# Sheet1.net
KiCad netlist of a schematic drawn in Altium Designer
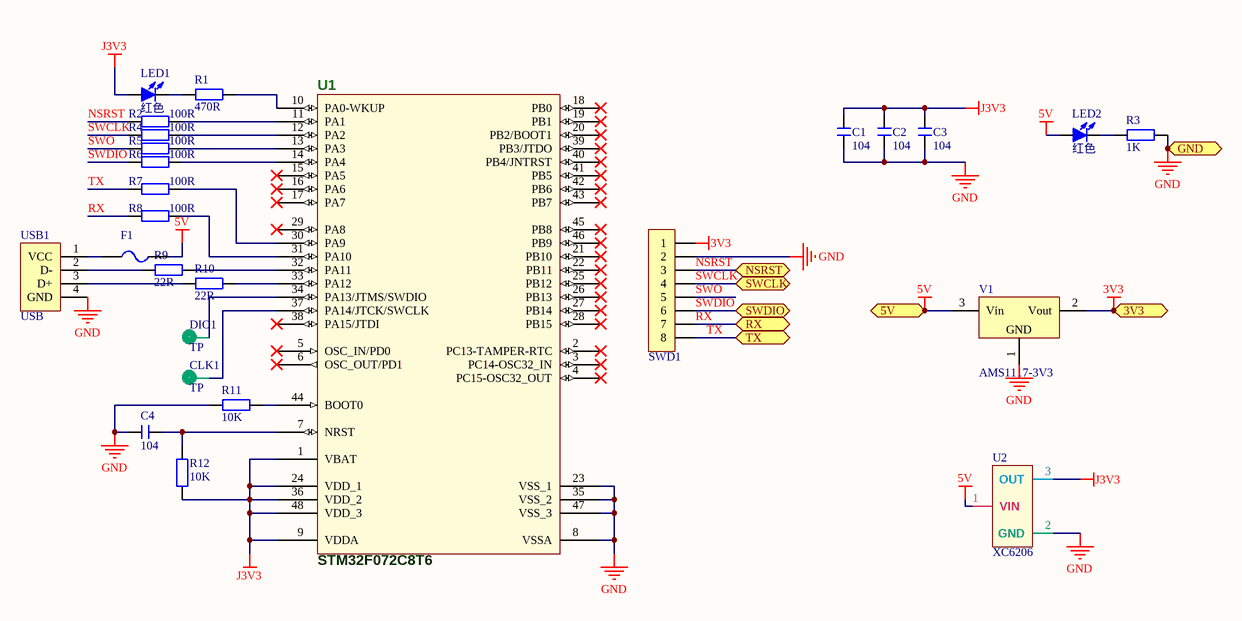
[diagram p0: Sheet1.SchDoc]

(export (version "E")
  (design (tool "Eeschema 10.0.6"))
  (components
    (comp (ref "C1")
      (value "104")
      (footprint "C 0805")
      (description "无极性贴片电容")
      (fields (field (name "版权归属") "黎明电子style"))
      (libsource (lib "电阻-电容-电感") (part "C"))
    )
    (comp (ref "C2")
      (value "104")
      (footprint "C 0805")
      (description "无极性贴片电容")
      (fields (field (name "版权归属") "黎明电子style"))
      (libsource (lib "电阻-电容-电感") (part "C"))
    )
    (comp (ref "C3")
      (value "104")
      (footprint "C 0805")
      (description "无极性贴片电容")
      (fields (field (name "版权归属") "黎明电子style"))
      (libsource (lib "电阻-电容-电感") (part "C"))
    )
    (comp (ref "C4")
      (value "104")
      (footprint "C 0805")
      (description "无极性贴片电容")
      (fields (field (name "版权归属") "黎明电子style"))
      (libsource (lib "电阻-电容-电感") (part "C"))
    )
    (comp (ref "CLK1") (value "TP") (footprint "TP") (libsource (lib "spotmini") (part "TP")))
    (comp (ref "DIO1") (value "TP") (footprint "TP") (libsource (lib "spotmini") (part "TP")))
    (comp (ref "F1")
      (value "~")
      (footprint "FU 0805")
      (description "贴片保险丝")
      (fields (field (name "版权归属") "黎明电子style"))
      (libsource (lib "保险丝-晶振") (part "FU"))
    )
    (comp (ref "LED1")
      (value "红色")
      (footprint "LED 0805G")
      (description "5mm草帽LED")
      (fields (field (name "版权归属") "黎明电子style"))
      (libsource (lib "LED") (part "LED-SH-5MM"))
    )
    (comp (ref "LED2")
      (value "红色")
      (footprint "LED 0805R")
      (description "5mm草帽LED")
      (fields (field (name "版权归属") "黎明电子style"))
      (libsource (lib "LED") (part "LED-SH-5MM"))
    )
    (comp (ref "R1")
      (value "470R")
      (footprint "R 0805-HP")
      (description "贴片电阻")
      (fields (field (name "版权归属") "黎明电子style"))
      (libsource (lib "电阻-电容-电感") (part "R"))
    )
    (comp (ref "R2")
      (value "100R")
      (footprint "R 0805-HP")
      (description "贴片电阻")
      (fields (field (name "版权归属") "黎明电子style"))
      (libsource (lib "电阻-电容-电感") (part "R"))
    )
    (comp (ref "R3")
      (value "1K")
      (footprint "R 0805-HP")
      (description "贴片电阻")
      (fields (field (name "版权归属") "黎明电子style"))
      (libsource (lib "电阻-电容-电感") (part "R"))
    )
    (comp (ref "R4")
      (value "100R")
      (footprint "R 0805-HP")
      (description "贴片电阻")
      (fields (field (name "版权归属") "黎明电子style"))
      (libsource (lib "电阻-电容-电感") (part "R"))
    )
    (comp (ref "R5")
      (value "100R")
      (footprint "R 0805-HP")
      (description "贴片电阻")
      (fields (field (name "版权归属") "黎明电子style"))
      (libsource (lib "电阻-电容-电感") (part "R"))
    )
    (comp (ref "R6")
      (value "100R")
      (footprint "R 0805-HP")
      (description "贴片电阻")
      (fields (field (name "版权归属") "黎明电子style"))
      (libsource (lib "电阻-电容-电感") (part "R"))
    )
    (comp (ref "R7")
      (value "100R")
      (footprint "R 0805-HP")
      (description "贴片电阻")
      (fields (field (name "版权归属") "黎明电子style"))
      (libsource (lib "电阻-电容-电感") (part "R"))
    )
    (comp (ref "R8")
      (value "100R")
      (footprint "R 0805-HP")
      (description "贴片电阻")
      (fields (field (name "版权归属") "黎明电子style"))
      (libsource (lib "电阻-电容-电感") (part "R"))
    )
    (comp (ref "R9")
      (value "22R")
      (footprint "R 0805-HP")
      (description "贴片电阻")
      (fields (field (name "版权归属") "黎明电子style"))
      (libsource (lib "电阻-电容-电感") (part "R"))
    )
    (comp (ref "R10")
      (value "22R")
      (footprint "R 0805-HP")
      (description "贴片电阻")
      (fields (field (name "版权归属") "黎明电子style"))
      (libsource (lib "电阻-电容-电感") (part "R"))
    )
    (comp (ref "R11")
      (value "10K")
      (footprint "R 0805-HP")
      (description "贴片电阻")
      (fields (field (name "版权归属") "黎明电子style"))
      (libsource (lib "电阻-电容-电感") (part "R"))
    )
    (comp (ref "R12")
      (value "10K")
      (footprint "R 0805-HP")
      (description "贴片电阻")
      (fields (field (name "版权归属") "黎明电子style"))
      (libsource (lib "电阻-电容-电感") (part "R"))
    )
    (comp (ref "SWD1")
      (value "HDR-1X8")
      (footprint "HDR-1X8")
      (description "8P接插件")
      (fields (field (name "版权归属") "黎明电子style"))
      (libsource (lib "接插件") (part "Header 8"))
    )
    (comp (ref "U1")
      (value "STM32F072C8T6")
      (footprint "LQFP48P")
      (libsource (lib "spotmini") (part "STM32F072C8T6"))
    )
    (comp (ref "U2") (value "XC6206") (footprint "XC6206") (libsource (lib "spotmini") (part "XC6206")))
    (comp (ref "USB1")
      (value "USB")
      (footprint "USB-B/S_A")
      (description "USB-B型母接口")
      (fields (field (name "版权归属") "黎明电子style"))
      (libsource (lib "接口类") (part "USB-B/S"))
    )
    (comp (ref "V1")
      (value "AMS1117-3V3")
      (footprint "SOT223_L")
      (description "三端稳压芯片")
      (fields (field (name "版权归属") "黎明电子style"))
      (libsource (lib "IC芯片") (part "AMS1117"))
    )
  )
  (nets
    (net (code "1") (name "/NSRST") (class "Default")
      (node (ref "R2") (pin "1") (pinfunction "1_1") (pintype "passive"))
      (node (ref "SWD1") (pin "3") (pinfunction "3_3") (pintype "passive"))
    )
    (net (code "2") (name "/RX") (class "Default")
      (node (ref "R8") (pin "1") (pinfunction "1_1") (pintype "passive"))
      (node (ref "SWD1") (pin "7") (pinfunction "7_7") (pintype "passive"))
    )
    (net (code "3") (name "/SWCLK") (class "Default")
      (node (ref "R4") (pin "1") (pinfunction "1_1") (pintype "passive"))
      (node (ref "SWD1") (pin "4") (pinfunction "4_4") (pintype "passive"))
    )
    (net (code "4") (name "/SWDIO") (class "Default")
      (node (ref "R6") (pin "1") (pinfunction "1_1") (pintype "passive"))
      (node (ref "SWD1") (pin "6") (pinfunction "6_6") (pintype "passive"))
    )
    (net (code "5") (name "/SWO") (class "Default")
      (node (ref "R5") (pin "1") (pinfunction "1_1") (pintype "passive"))
      (node (ref "SWD1") (pin "5") (pinfunction "5_5") (pintype "passive"))
    )
    (net (code "6") (name "/TX") (class "Default")
      (node (ref "R7") (pin "1") (pinfunction "1_1") (pintype "passive"))
      (node (ref "SWD1") (pin "8") (pinfunction "8_8") (pintype "passive"))
    )
    (net (code "7") (name "3V3") (class "Default")
      (node (ref "SWD1") (pin "1") (pinfunction "1_1") (pintype "passive"))
      (node (ref "V1") (pin "2") (pinfunction "Vout_2") (pintype "passive"))
    )
    (net (code "8") (name "5V") (class "Default")
      (node (ref "F1") (pin "2") (pinfunction "2_2") (pintype "passive"))
      (node (ref "LED2") (pin "1") (pinfunction "A_1") (pintype "passive"))
      (node (ref "U2") (pin "1") (pinfunction "VIN_1") (pintype "passive"))
      (node (ref "V1") (pin "3") (pinfunction "Vin_3") (pintype "passive"))
    )
    (net (code "9") (name "GND") (class "Default")
      (node (ref "C1") (pin "1") (pinfunction "1_1") (pintype "passive"))
      (node (ref "C2") (pin "1") (pinfunction "1_1") (pintype "passive"))
      (node (ref "C3") (pin "1") (pinfunction "1_1") (pintype "passive"))
      (node (ref "C4") (pin "1") (pinfunction "1_1") (pintype "passive"))
      (node (ref "R11") (pin "1") (pinfunction "1_1") (pintype "passive"))
      (node (ref "R3") (pin "2") (pinfunction "2_2") (pintype "passive"))
      (node (ref "SWD1") (pin "2") (pinfunction "2_2") (pintype "passive"))
      (node (ref "U1") (pin "23") (pinfunction "VSS_1_23") (pintype "power_in"))
      (node (ref "U1") (pin "35") (pinfunction "VSS_2_35") (pintype "power_in"))
      (node (ref "U1") (pin "47") (pinfunction "VSS_3_47") (pintype "power_in"))
      (node (ref "U1") (pin "8") (pinfunction "VSSA_8") (pintype "power_in"))
      (node (ref "U2") (pin "2") (pinfunction "GND_2") (pintype "passive"))
      (node (ref "USB1") (pin "4") (pinfunction "GND_4") (pintype "passive"))
      (node (ref "V1") (pin "1") (pinfunction "GND_1") (pintype "passive"))
    )
    (net (code "10") (name "J3V3") (class "Default")
      (node (ref "C1") (pin "2") (pinfunction "2_2") (pintype "passive"))
      (node (ref "C2") (pin "2") (pinfunction "2_2") (pintype "passive"))
      (node (ref "C3") (pin "2") (pinfunction "2_2") (pintype "passive"))
      (node (ref "LED1") (pin "1") (pinfunction "A_1") (pintype "passive"))
      (node (ref "R12") (pin "1") (pinfunction "1_1") (pintype "passive"))
      (node (ref "U1") (pin "1") (pinfunction "VBAT_1") (pintype "power_in"))
      (node (ref "U1") (pin "24") (pinfunction "VDD_1_24") (pintype "power_in"))
      (node (ref "U1") (pin "36") (pinfunction "VDD_2_36") (pintype "power_in"))
      (node (ref "U1") (pin "48") (pinfunction "VDD_3_48") (pintype "power_in"))
      (node (ref "U1") (pin "9") (pinfunction "VDDA_9") (pintype "power_in"))
      (node (ref "U2") (pin "3") (pinfunction "OUT_3") (pintype "passive"))
    )
    (net (code "11") (name "Net-(LED1-K)") (class "Default")
      (node (ref "LED1") (pin "2") (pinfunction "K_2") (pintype "passive"))
      (node (ref "R1") (pin "1") (pinfunction "1_1") (pintype "passive"))
    )
    (net (code "12") (name "Net-(LED2-K)") (class "Default")
      (node (ref "LED2") (pin "2") (pinfunction "K_2") (pintype "passive"))
      (node (ref "R3") (pin "1") (pinfunction "1_1") (pintype "passive"))
    )
    (net (code "13") (name "Net-(U1-BOOT0)") (class "Default")
      (node (ref "R11") (pin "2") (pinfunction "2_2") (pintype "passive"))
      (node (ref "U1") (pin "44") (pinfunction "BOOT0_44") (pintype "input"))
    )
    (net (code "14") (name "Net-(U1-NRST)") (class "Default")
      (node (ref "C4") (pin "2") (pinfunction "2_2") (pintype "passive"))
      (node (ref "R12") (pin "2") (pinfunction "2_2") (pintype "passive"))
      (node (ref "U1") (pin "7") (pinfunction "NRST_7") (pintype "bidirectional"))
    )
    (net (code "15") (name "Net-(U1-PA0-WKUP)") (class "Default")
      (node (ref "R1") (pin "2") (pinfunction "2_2") (pintype "passive"))
      (node (ref "U1") (pin "10") (pinfunction "PA0-WKUP_10") (pintype "bidirectional"))
    )
    (net (code "16") (name "Net-(U1-PA1)") (class "Default")
      (node (ref "R2") (pin "2") (pinfunction "2_2") (pintype "passive"))
      (node (ref "U1") (pin "11") (pinfunction "PA1_11") (pintype "bidirectional"))
    )
    (net (code "17") (name "Net-(U1-PA2)") (class "Default")
      (node (ref "R4") (pin "2") (pinfunction "2_2") (pintype "passive"))
      (node (ref "U1") (pin "12") (pinfunction "PA2_12") (pintype "bidirectional"))
    )
    (net (code "18") (name "Net-(U1-PA3)") (class "Default")
      (node (ref "R5") (pin "2") (pinfunction "2_2") (pintype "passive"))
      (node (ref "U1") (pin "13") (pinfunction "PA3_13") (pintype "bidirectional"))
    )
    (net (code "19") (name "Net-(U1-PA4)") (class "Default")
      (node (ref "R6") (pin "2") (pinfunction "2_2") (pintype "passive"))
      (node (ref "U1") (pin "14") (pinfunction "PA4_14") (pintype "bidirectional"))
    )
    (net (code "20") (name "Net-(U1-PA9)") (class "Default")
      (node (ref "R7") (pin "2") (pinfunction "2_2") (pintype "passive"))
      (node (ref "U1") (pin "30") (pinfunction "PA9_30") (pintype "bidirectional"))
    )
    (net (code "21") (name "Net-(U1-PA10)") (class "Default")
      (node (ref "R8") (pin "2") (pinfunction "2_2") (pintype "passive"))
      (node (ref "U1") (pin "31") (pinfunction "PA10_31") (pintype "bidirectional"))
    )
    (net (code "22") (name "Net-(U1-PA11)") (class "Default")
      (node (ref "R9") (pin "2") (pinfunction "2_2") (pintype "passive"))
      (node (ref "U1") (pin "32") (pinfunction "PA11_32") (pintype "bidirectional"))
    )
    (net (code "23") (name "Net-(U1-PA12)") (class "Default")
      (node (ref "R10") (pin "2") (pinfunction "2_2") (pintype "passive"))
      (node (ref "U1") (pin "33") (pinfunction "PA12_33") (pintype "bidirectional"))
    )
    (net (code "24") (name "Net-(U1-PA13{slash}JTMS{slash}SWDIO)") (class "Default")
      (node (ref "DIO1") (pin "1") (pinfunction "1_1") (pintype "passive"))
      (node (ref "U1") (pin "34") (pinfunction "PA13/JTMS/SWDIO_34") (pintype "bidirectional"))
    )
    (net (code "25") (name "Net-(U1-PA14{slash}JTCK{slash}SWCLK)") (class "Default")
      (node (ref "CLK1") (pin "1") (pinfunction "1_1") (pintype "passive"))
      (node (ref "U1") (pin "37") (pinfunction "PA14/JTCK/SWCLK_37") (pintype "bidirectional"))
    )
    (net (code "26") (name "Net-(USB1-D+)") (class "Default")
      (node (ref "R10") (pin "1") (pinfunction "1_1") (pintype "passive"))
      (node (ref "USB1") (pin "3") (pinfunction "D+_3") (pintype "passive"))
    )
    (net (code "27") (name "Net-(USB1-D-)") (class "Default")
      (node (ref "R9") (pin "1") (pinfunction "1_1") (pintype "passive"))
      (node (ref "USB1") (pin "2") (pinfunction "D-_2") (pintype "passive"))
    )
    (net (code "28") (name "Net-(USB1-VCC)") (class "Default")
      (node (ref "F1") (pin "1") (pinfunction "1_1") (pintype "passive"))
      (node (ref "USB1") (pin "1") (pinfunction "VCC_1") (pintype "passive"))
    )
    (net (code "29") (name "unconnected-(U1-OSC_IN{slash}PD0-Pad5)") (class "Default")
      (node (ref "U1") (pin "5") (pinfunction "OSC_IN/PD0_5") (pintype "input+no_connect"))
    )
    (net (code "30") (name "unconnected-(U1-OSC_OUT{slash}PD1-Pad6)") (class "Default")
      (node (ref "U1") (pin "6") (pinfunction "OSC_OUT/PD1_6") (pintype "output+no_connect"))
    )
    (net (code "31") (name "unconnected-(U1-PA5-Pad15)") (class "Default")
      (node (ref "U1") (pin "15") (pinfunction "PA5_15") (pintype "bidirectional+no_connect"))
    )
    (net (code "32") (name "unconnected-(U1-PA6-Pad16)") (class "Default")
      (node (ref "U1") (pin "16") (pinfunction "PA6_16") (pintype "bidirectional+no_connect"))
    )
    (net (code "33") (name "unconnected-(U1-PA7-Pad17)") (class "Default")
      (node (ref "U1") (pin "17") (pinfunction "PA7_17") (pintype "bidirectional+no_connect"))
    )
    (net (code "34") (name "unconnected-(U1-PA8-Pad29)") (class "Default")
      (node (ref "U1") (pin "29") (pinfunction "PA8_29") (pintype "bidirectional+no_connect"))
    )
    (net (code "35") (name "unconnected-(U1-PA15{slash}JTDI-Pad38)") (class "Default")
      (node (ref "U1") (pin "38") (pinfunction "PA15/JTDI_38") (pintype "bidirectional+no_connect"))
    )
    (net (code "36") (name "unconnected-(U1-PB0-Pad18)") (class "Default")
      (node (ref "U1") (pin "18") (pinfunction "PB0_18") (pintype "bidirectional+no_connect"))
    )
    (net (code "37") (name "unconnected-(U1-PB1-Pad19)") (class "Default")
      (node (ref "U1") (pin "19") (pinfunction "PB1_19") (pintype "bidirectional+no_connect"))
    )
    (net (code "38") (name "unconnected-(U1-PB2{slash}BOOT1-Pad20)") (class "Default")
      (node (ref "U1") (pin "20") (pinfunction "PB2/BOOT1_20") (pintype "bidirectional+no_connect"))
    )
    (net (code "39") (name "unconnected-(U1-PB3{slash}JTDO-Pad39)") (class "Default")
      (node (ref "U1") (pin "39") (pinfunction "PB3/JTDO_39") (pintype "bidirectional+no_connect"))
    )
    (net (code "40") (name "unconnected-(U1-PB4{slash}JNTRST-Pad40)") (class "Default")
      (node (ref "U1") (pin "40") (pinfunction "PB4/JNTRST_40") (pintype "bidirectional+no_connect"))
    )
    (net (code "41") (name "unconnected-(U1-PB5-Pad41)") (class "Default")
      (node (ref "U1") (pin "41") (pinfunction "PB5_41") (pintype "bidirectional+no_connect"))
    )
    (net (code "42") (name "unconnected-(U1-PB6-Pad42)") (class "Default")
      (node (ref "U1") (pin "42") (pinfunction "PB6_42") (pintype "bidirectional+no_connect"))
    )
    (net (code "43") (name "unconnected-(U1-PB7-Pad43)") (class "Default")
      (node (ref "U1") (pin "43") (pinfunction "PB7_43") (pintype "bidirectional+no_connect"))
    )
    (net (code "44") (name "unconnected-(U1-PB8-Pad45)") (class "Default")
      (node (ref "U1") (pin "45") (pinfunction "PB8_45") (pintype "bidirectional+no_connect"))
    )
    (net (code "45") (name "unconnected-(U1-PB9-Pad46)") (class "Default")
      (node (ref "U1") (pin "46") (pinfunction "PB9_46") (pintype "bidirectional+no_connect"))
    )
    (net (code "46") (name "unconnected-(U1-PB10-Pad21)") (class "Default")
      (node (ref "U1") (pin "21") (pinfunction "PB10_21") (pintype "bidirectional+no_connect"))
    )
    (net (code "47") (name "unconnected-(U1-PB11-Pad22)") (class "Default")
      (node (ref "U1") (pin "22") (pinfunction "PB11_22") (pintype "bidirectional+no_connect"))
    )
    (net (code "48") (name "unconnected-(U1-PB12-Pad25)") (class "Default")
      (node (ref "U1") (pin "25") (pinfunction "PB12_25") (pintype "bidirectional+no_connect"))
    )
    (net (code "49") (name "unconnected-(U1-PB13-Pad26)") (class "Default")
      (node (ref "U1") (pin "26") (pinfunction "PB13_26") (pintype "bidirectional+no_connect"))
    )
    (net (code "50") (name "unconnected-(U1-PB14-Pad27)") (class "Default")
      (node (ref "U1") (pin "27") (pinfunction "PB14_27") (pintype "bidirectional+no_connect"))
    )
    (net (code "51") (name "unconnected-(U1-PB15-Pad28)") (class "Default")
      (node (ref "U1") (pin "28") (pinfunction "PB15_28") (pintype "bidirectional+no_connect"))
    )
    (net (code "52") (name "unconnected-(U1-PC13-TAMPER-RTC-Pad2)") (class "Default")
      (node (ref "U1") (pin "2") (pinfunction "PC13-TAMPER-RTC_2") (pintype "bidirectional+no_connect"))
    )
    (net (code "53") (name "unconnected-(U1-PC14-OSC32_IN-Pad3)") (class "Default")
      (node (ref "U1") (pin "3") (pinfunction "PC14-OSC32_IN_3") (pintype "bidirectional+no_connect"))
    )
    (net (code "54") (name "unconnected-(U1-PC15-OSC32_OUT-Pad4)") (class "Default")
      (node (ref "U1") (pin "4") (pinfunction "PC15-OSC32_OUT_4") (pintype "bidirectional+no_connect"))
    )
  )
)
